# Lithium_Battery_Charger.net
KiCad netlist of a schematic drawn in Altium Designer
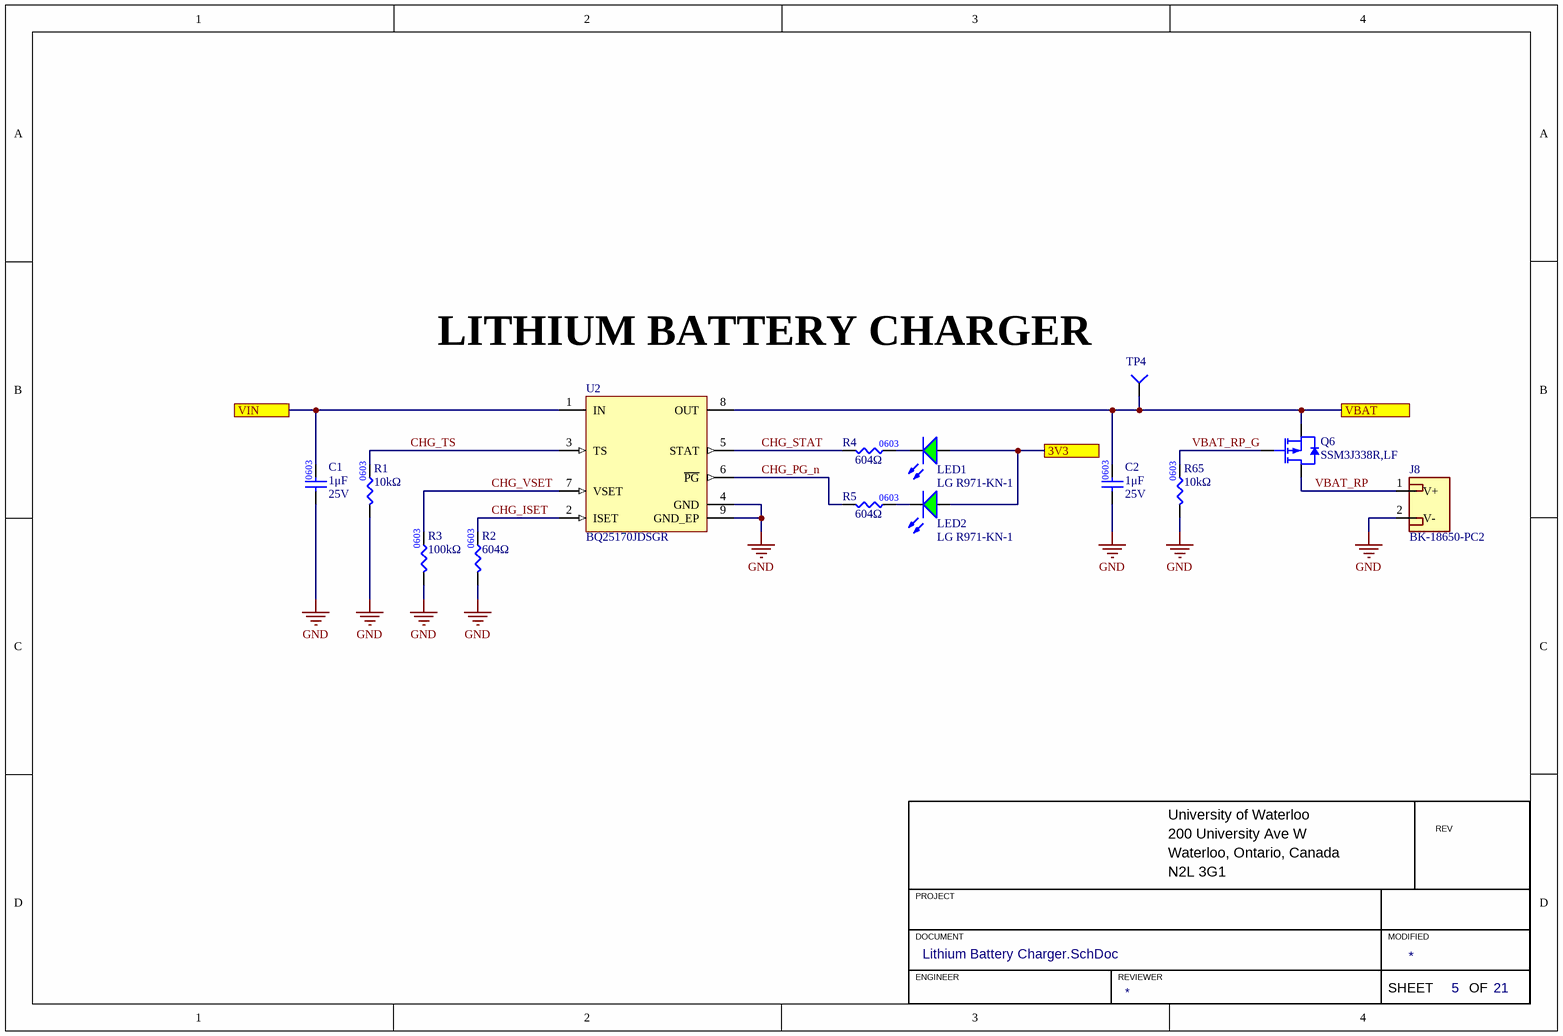
[diagram p0: Lithium Battery Charger.SchDoc]

(export (version "E")
  (design (tool "Eeschema 10.0.6"))
  (components
    (comp (ref "C1")
      (value "1μF")
      (footprint "CAP0603")
      (description "CAP CER 1UF 25V X5R 0603")
      (fields (field (name "VOLTAGE RATING") "25V") (field (name "Comment") "CAP_1uF_25V_0603"))
      (libsource (lib "Personal_Schematic_Library_2022") (part "CAP_1uF_25V_0603"))
    )
    (comp (ref "C2")
      (value "1μF")
      (footprint "CAP0603")
      (description "CAP CER 1UF 25V X5R 0603")
      (fields (field (name "VOLTAGE RATING") "25V") (field (name "Comment") "CAP_1uF_25V_0603"))
      (libsource (lib "Personal_Schematic_Library_2022") (part "CAP_1uF_25V_0603"))
    )
    (comp (ref "J8")
      (value "CON_2POS_XT90")
      (footprint "MPD_18650-PC2")
      (description "BATTERY HOLDER 18650 PC PIN")
      (fields (field (name "MANUFACTURER PART NUMBER 1") "BK-18650-PC2"))
      (libsource (lib "Personal_Schematic_Library_2022") (part "CON_2POS_18650"))
    )
    (comp (ref "LED1")
      (value "LED_GREEN_0805")
      (footprint "LED_0805_GREEN")
      (description "LED GREEN DIFFUSED 0805 SMD")
      (fields (field (name "MANUFACTURER PART NUMBER 1") "LG R971-KN-1"))
      (libsource (lib "Personal_Schematic_Library_2022") (part "LED_GREEN_0805"))
    )
    (comp (ref "LED2")
      (value "LED_GREEN_0805")
      (footprint "LED_0805_GREEN")
      (description "LED GREEN DIFFUSED 0805 SMD")
      (fields (field (name "MANUFACTURER PART NUMBER 1") "LG R971-KN-1"))
      (libsource (lib "Personal_Schematic_Library_2022") (part "LED_GREEN_0805"))
    )
    (comp (ref "Q6")
      (value "PMOS_12V_6A")
      (footprint "DIO-INC_SOT23")
      (description "MOSFET P-CH 12V 6A SOT23F")
      (fields (field (name "MANUFACTURER PART NUMBER 1") "SSM3J338R,LF"))
      (libsource (lib "Personal_Schematic_Library_2022") (part "PMOS_12V_6A"))
    )
    (comp (ref "R1")
      (value "10kΩ")
      (footprint "RES0603")
      (description "RES 10K OHM 1% 1/8W 0603")
      (fields (field (name "Comment") "RES_10kΩ_0603_1%"))
      (libsource (lib "Personal_Schematic_Library_2022") (part "RES_10kΩ_0603_1%"))
    )
    (comp (ref "R2")
      (value "604Ω")
      (footprint "RES0603")
      (description "RES 604 OHM 1% 1/10W 0603")
      (fields (field (name "Comment") "RES_604Ω_0603_1%"))
      (libsource (lib "Personal_Schematic_Library_2022") (part "RES_604Ω_0603_1%"))
    )
    (comp (ref "R3")
      (value "100kΩ")
      (footprint "RES0603")
      (description "RES 100K OHM 1% 1/10W 0603")
      (fields (field (name "Comment") "RES_100kΩ_0603_1%"))
      (libsource (lib "Personal_Schematic_Library_2022") (part "RES_100kΩ_0603_1%"))
    )
    (comp (ref "R4")
      (value "604Ω")
      (footprint "RES0603")
      (description "RES 604 OHM 1% 1/10W 0603")
      (fields (field (name "Comment") "RES_604Ω_0603_1%"))
      (libsource (lib "Personal_Schematic_Library_2022") (part "RES_604Ω_0603_1%"))
    )
    (comp (ref "R5")
      (value "604Ω")
      (footprint "RES0603")
      (description "RES 604 OHM 1% 1/10W 0603")
      (fields (field (name "Comment") "RES_604Ω_0603_1%"))
      (libsource (lib "Personal_Schematic_Library_2022") (part "RES_604Ω_0603_1%"))
    )
    (comp (ref "R65")
      (value "10kΩ")
      (footprint "RES0603")
      (description "RES 10K OHM 1% 1/8W 0603")
      (fields (field (name "Comment") "RES_10kΩ_0603_1%"))
      (libsource (lib "Personal_Schematic_Library_2022") (part "RES_10kΩ_0603_1%"))
    )
    (comp (ref "TP4")
      (value "TESTPOINT_KEYSTONE_LOOP")
      (footprint "KEYSTONE_5019")
      (description "PC TEST POINT MINIATURE")
      (libsource (lib "Personal_Schematic_Library_2022") (part "TESTPOINT_KEYSTONE_LOOP"))
    )
    (comp (ref "U2")
      (value "BQ25170JDSGR")
      (footprint "TI_8-WSON")
      (description "IC BATTERY MANAGEMENT")
      (libsource (lib "Personal_Schematic_Library_2022") (part "BQ25170JDSGR"))
    )
  )
  (nets
    (net (code "1") (name "/3V3") (class "Default")
      (node (ref "LED1") (pin "1") (pinfunction "A_1") (pintype "passive"))
      (node (ref "LED2") (pin "1") (pinfunction "A_1") (pintype "passive"))
    )
    (net (code "2") (name "/CHG_ISET") (class "Default")
      (node (ref "R2") (pin "2") (pinfunction "2_2") (pintype "passive"))
      (node (ref "U2") (pin "2") (pinfunction "ISET_2") (pintype "input"))
    )
    (net (code "3") (name "/CHG_PG_n") (class "Default")
      (node (ref "R5") (pin "1") (pinfunction "1_1") (pintype "passive"))
      (node (ref "U2") (pin "6") (pinfunction "~{PG}_6") (pintype "output"))
    )
    (net (code "4") (name "/CHG_STAT") (class "Default")
      (node (ref "R4") (pin "1") (pinfunction "1_1") (pintype "passive"))
      (node (ref "U2") (pin "5") (pinfunction "STAT_5") (pintype "output"))
    )
    (net (code "5") (name "/CHG_TS") (class "Default")
      (node (ref "R1") (pin "2") (pinfunction "2_2") (pintype "passive"))
      (node (ref "U2") (pin "3") (pinfunction "TS_3") (pintype "input"))
    )
    (net (code "6") (name "/CHG_VSET") (class "Default")
      (node (ref "R3") (pin "2") (pinfunction "2_2") (pintype "passive"))
      (node (ref "U2") (pin "7") (pinfunction "VSET_7") (pintype "input"))
    )
    (net (code "7") (name "/VBAT") (class "Default")
      (node (ref "C2") (pin "2") (pinfunction "2_2") (pintype "passive"))
      (node (ref "Q6") (pin "2") (pinfunction "Source_2") (pintype "passive"))
      (node (ref "TP4") (pin "1") (pinfunction "=value_1") (pintype "passive"))
      (node (ref "U2") (pin "8") (pinfunction "OUT_8") (pintype "power_in"))
    )
    (net (code "8") (name "/VBAT_RP") (class "Default")
      (node (ref "J8") (pin "1") (pinfunction "V+_1") (pintype "power_in"))
      (node (ref "Q6") (pin "3") (pinfunction "Drain_3") (pintype "passive"))
    )
    (net (code "9") (name "/VBAT_RP_G") (class "Default")
      (node (ref "Q6") (pin "1") (pinfunction "Gate_1") (pintype "passive"))
      (node (ref "R65") (pin "2") (pinfunction "2_2") (pintype "passive"))
    )
    (net (code "10") (name "/VIN") (class "Default")
      (node (ref "C1") (pin "2") (pinfunction "2_2") (pintype "passive"))
      (node (ref "U2") (pin "1") (pinfunction "IN_1") (pintype "power_in"))
    )
    (net (code "11") (name "GND") (class "Default")
      (node (ref "C1") (pin "1") (pinfunction "1_1") (pintype "passive"))
      (node (ref "C2") (pin "1") (pinfunction "1_1") (pintype "passive"))
      (node (ref "J8") (pin "2") (pinfunction "V-_2") (pintype "power_in"))
      (node (ref "R1") (pin "1") (pinfunction "1_1") (pintype "passive"))
      (node (ref "R2") (pin "1") (pinfunction "1_1") (pintype "passive"))
      (node (ref "R3") (pin "1") (pinfunction "1_1") (pintype "passive"))
      (node (ref "R65") (pin "1") (pinfunction "1_1") (pintype "passive"))
      (node (ref "U2") (pin "4") (pinfunction "GND_4") (pintype "power_in"))
      (node (ref "U2") (pin "9") (pinfunction "GND_EP_9") (pintype "power_in"))
    )
    (net (code "12") (name "Net-(LED1-K)") (class "Default")
      (node (ref "LED1") (pin "2") (pinfunction "K_2") (pintype "passive"))
      (node (ref "R4") (pin "2") (pinfunction "2_2") (pintype "passive"))
    )
    (net (code "13") (name "Net-(LED2-K)") (class "Default")
      (node (ref "LED2") (pin "2") (pinfunction "K_2") (pintype "passive"))
      (node (ref "R5") (pin "2") (pinfunction "2_2") (pintype "passive"))
    )
  )
)
